# Backplane_extRefV4.net
KiCad netlist of a schematic drawn in EAGLE
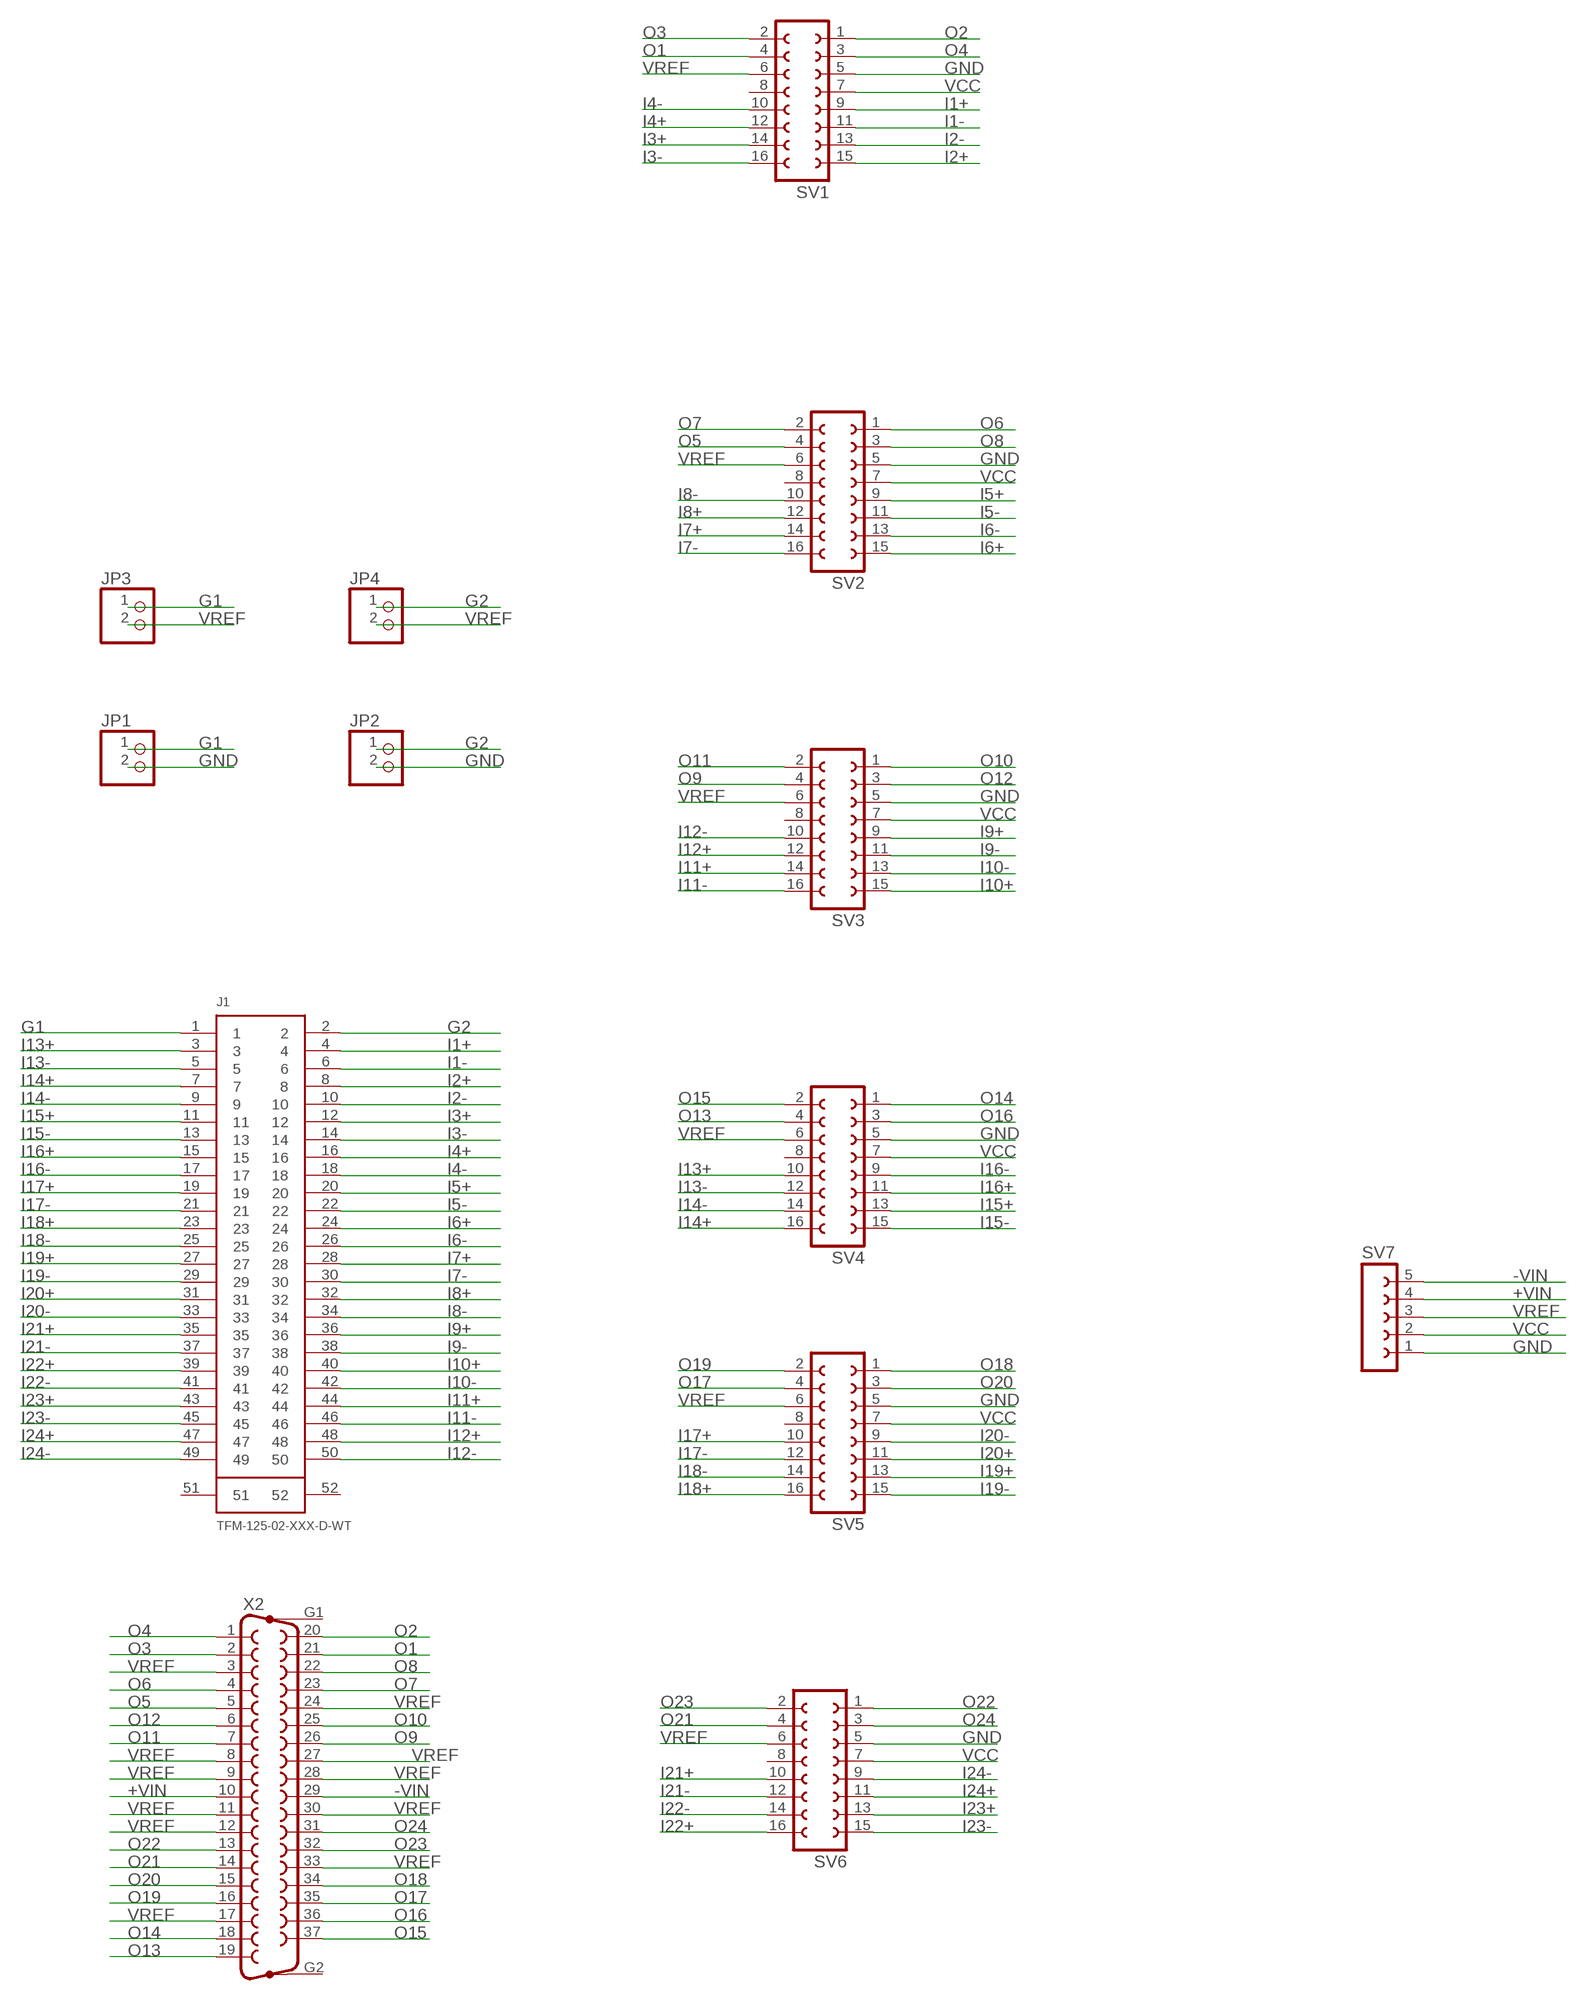
[diagram p0: schematic, sheet 1]

(export (version "E")
  (design (tool "Eeschema 10.0.6"))
  (components
    (comp (ref "J1")
      (value "TFM-125-02-XXX-D-WT")
      (footprint "eagle-import:TFM-125-02-XXX-D-WT")
      (libsource (lib "eagle-import") (part "TFM-125-02-XXX-D-WT"))
    )
    (comp (ref "JP1")
      (value "PINHD-1X2")
      (footprint "eagle-import:1X02")
      (libsource (lib "eagle-import") (part "PINHD-1X2"))
    )
    (comp (ref "JP2")
      (value "PINHD-1X2")
      (footprint "eagle-import:1X02")
      (libsource (lib "eagle-import") (part "PINHD-1X2"))
    )
    (comp (ref "JP3")
      (value "PINHD-1X2")
      (footprint "eagle-import:1X02")
      (libsource (lib "eagle-import") (part "PINHD-1X2"))
    )
    (comp (ref "JP4")
      (value "PINHD-1X2")
      (footprint "eagle-import:1X02")
      (libsource (lib "eagle-import") (part "PINHD-1X2"))
    )
    (comp (ref "SV1")
      (value "FE08-2")
      (footprint "eagle-import:FE08-2")
      (libsource (lib "eagle-import") (part "FE08-2"))
    )
    (comp (ref "SV2")
      (value "FE08-2")
      (footprint "eagle-import:FE08-2")
      (libsource (lib "eagle-import") (part "FE08-2"))
    )
    (comp (ref "SV3")
      (value "FE08-2")
      (footprint "eagle-import:FE08-2")
      (libsource (lib "eagle-import") (part "FE08-2"))
    )
    (comp (ref "SV4")
      (value "FE08-2")
      (footprint "eagle-import:FE08-2")
      (libsource (lib "eagle-import") (part "FE08-2"))
    )
    (comp (ref "SV5")
      (value "FE08-2")
      (footprint "eagle-import:FE08-2")
      (libsource (lib "eagle-import") (part "FE08-2"))
    )
    (comp (ref "SV6")
      (value "FE08-2")
      (footprint "eagle-import:FE08-2")
      (libsource (lib "eagle-import") (part "FE08-2"))
    )
    (comp (ref "SV7")
      (value "FE05-1")
      (footprint "eagle-import:FE05-1")
      (libsource (lib "eagle-import") (part "FE05-1"))
    )
    (comp (ref "X2")
      (value "F37HP")
      (footprint "eagle-import:F37HP")
      (libsource (lib "eagle-import") (part "F37HP"))
    )
  )
  (nets
    (net (code "1") (name "/+VIN") (class "Default")
      (node (ref "SV7") (pin "4") (pinfunction "4_4") (pintype "passive"))
      (node (ref "X2") (pin "10") (pinfunction "10_10") (pintype "passive"))
    )
    (net (code "2") (name "/-VIN") (class "Default")
      (node (ref "SV7") (pin "5") (pinfunction "5_5") (pintype "passive"))
      (node (ref "X2") (pin "29") (pinfunction "29_29") (pintype "passive"))
    )
    (net (code "3") (name "/G1") (class "Default")
      (node (ref "J1") (pin "1") (pinfunction "1_1") (pintype "bidirectional"))
      (node (ref "JP1") (pin "1") (pinfunction "1_1") (pintype "passive"))
      (node (ref "JP3") (pin "1") (pinfunction "1_1") (pintype "passive"))
    )
    (net (code "4") (name "/G2") (class "Default")
      (node (ref "J1") (pin "2") (pinfunction "2_2") (pintype "bidirectional"))
      (node (ref "JP2") (pin "1") (pinfunction "1_1") (pintype "passive"))
      (node (ref "JP4") (pin "1") (pinfunction "1_1") (pintype "passive"))
    )
    (net (code "5") (name "/GND") (class "Default")
      (node (ref "JP1") (pin "2") (pinfunction "2_2") (pintype "passive"))
      (node (ref "JP2") (pin "2") (pinfunction "2_2") (pintype "passive"))
      (node (ref "SV1") (pin "5") (pinfunction "5_5") (pintype "passive"))
      (node (ref "SV2") (pin "5") (pinfunction "5_5") (pintype "passive"))
      (node (ref "SV3") (pin "5") (pinfunction "5_5") (pintype "passive"))
      (node (ref "SV4") (pin "5") (pinfunction "5_5") (pintype "passive"))
      (node (ref "SV5") (pin "5") (pinfunction "5_5") (pintype "passive"))
      (node (ref "SV6") (pin "5") (pinfunction "5_5") (pintype "passive"))
      (node (ref "SV7") (pin "1") (pinfunction "1_1") (pintype "passive"))
    )
    (net (code "6") (name "/I1+") (class "Default")
      (node (ref "J1") (pin "4") (pinfunction "4_4") (pintype "bidirectional"))
      (node (ref "SV1") (pin "9") (pinfunction "9_9") (pintype "passive"))
    )
    (net (code "7") (name "/I1-") (class "Default")
      (node (ref "J1") (pin "6") (pinfunction "6_6") (pintype "bidirectional"))
      (node (ref "SV1") (pin "11") (pinfunction "11_11") (pintype "passive"))
    )
    (net (code "8") (name "/I2+") (class "Default")
      (node (ref "J1") (pin "8") (pinfunction "8_8") (pintype "bidirectional"))
      (node (ref "SV1") (pin "15") (pinfunction "15_15") (pintype "passive"))
    )
    (net (code "9") (name "/I2-") (class "Default")
      (node (ref "J1") (pin "10") (pinfunction "10_10") (pintype "bidirectional"))
      (node (ref "SV1") (pin "13") (pinfunction "13_13") (pintype "passive"))
    )
    (net (code "10") (name "/I3+") (class "Default")
      (node (ref "J1") (pin "12") (pinfunction "12_12") (pintype "bidirectional"))
      (node (ref "SV1") (pin "14") (pinfunction "14_14") (pintype "passive"))
    )
    (net (code "11") (name "/I3-") (class "Default")
      (node (ref "J1") (pin "14") (pinfunction "14_14") (pintype "bidirectional"))
      (node (ref "SV1") (pin "16") (pinfunction "16_16") (pintype "passive"))
    )
    (net (code "12") (name "/I4+") (class "Default")
      (node (ref "J1") (pin "16") (pinfunction "16_16") (pintype "bidirectional"))
      (node (ref "SV1") (pin "12") (pinfunction "12_12") (pintype "passive"))
    )
    (net (code "13") (name "/I4-") (class "Default")
      (node (ref "J1") (pin "18") (pinfunction "18_18") (pintype "bidirectional"))
      (node (ref "SV1") (pin "10") (pinfunction "10_10") (pintype "passive"))
    )
    (net (code "14") (name "/I5+") (class "Default")
      (node (ref "J1") (pin "20") (pinfunction "20_20") (pintype "bidirectional"))
      (node (ref "SV2") (pin "9") (pinfunction "9_9") (pintype "passive"))
    )
    (net (code "15") (name "/I5-") (class "Default")
      (node (ref "J1") (pin "22") (pinfunction "22_22") (pintype "bidirectional"))
      (node (ref "SV2") (pin "11") (pinfunction "11_11") (pintype "passive"))
    )
    (net (code "16") (name "/I6+") (class "Default")
      (node (ref "J1") (pin "24") (pinfunction "24_24") (pintype "bidirectional"))
      (node (ref "SV2") (pin "15") (pinfunction "15_15") (pintype "passive"))
    )
    (net (code "17") (name "/I6-") (class "Default")
      (node (ref "J1") (pin "26") (pinfunction "26_26") (pintype "bidirectional"))
      (node (ref "SV2") (pin "13") (pinfunction "13_13") (pintype "passive"))
    )
    (net (code "18") (name "/I7+") (class "Default")
      (node (ref "J1") (pin "28") (pinfunction "28_28") (pintype "bidirectional"))
      (node (ref "SV2") (pin "14") (pinfunction "14_14") (pintype "passive"))
    )
    (net (code "19") (name "/I7-") (class "Default")
      (node (ref "J1") (pin "30") (pinfunction "30_30") (pintype "bidirectional"))
      (node (ref "SV2") (pin "16") (pinfunction "16_16") (pintype "passive"))
    )
    (net (code "20") (name "/I8+") (class "Default")
      (node (ref "J1") (pin "32") (pinfunction "32_32") (pintype "bidirectional"))
      (node (ref "SV2") (pin "12") (pinfunction "12_12") (pintype "passive"))
    )
    (net (code "21") (name "/I8-") (class "Default")
      (node (ref "J1") (pin "34") (pinfunction "34_34") (pintype "bidirectional"))
      (node (ref "SV2") (pin "10") (pinfunction "10_10") (pintype "passive"))
    )
    (net (code "22") (name "/I9+") (class "Default")
      (node (ref "J1") (pin "36") (pinfunction "36_36") (pintype "bidirectional"))
      (node (ref "SV3") (pin "9") (pinfunction "9_9") (pintype "passive"))
    )
    (net (code "23") (name "/I9-") (class "Default")
      (node (ref "J1") (pin "38") (pinfunction "38_38") (pintype "bidirectional"))
      (node (ref "SV3") (pin "11") (pinfunction "11_11") (pintype "passive"))
    )
    (net (code "24") (name "/I10+") (class "Default")
      (node (ref "J1") (pin "40") (pinfunction "40_40") (pintype "bidirectional"))
      (node (ref "SV3") (pin "15") (pinfunction "15_15") (pintype "passive"))
    )
    (net (code "25") (name "/I10-") (class "Default")
      (node (ref "J1") (pin "42") (pinfunction "42_42") (pintype "bidirectional"))
      (node (ref "SV3") (pin "13") (pinfunction "13_13") (pintype "passive"))
    )
    (net (code "26") (name "/I11+") (class "Default")
      (node (ref "J1") (pin "44") (pinfunction "44_44") (pintype "bidirectional"))
      (node (ref "SV3") (pin "14") (pinfunction "14_14") (pintype "passive"))
    )
    (net (code "27") (name "/I11-") (class "Default")
      (node (ref "J1") (pin "46") (pinfunction "46_46") (pintype "bidirectional"))
      (node (ref "SV3") (pin "16") (pinfunction "16_16") (pintype "passive"))
    )
    (net (code "28") (name "/I12+") (class "Default")
      (node (ref "J1") (pin "48") (pinfunction "48_48") (pintype "bidirectional"))
      (node (ref "SV3") (pin "12") (pinfunction "12_12") (pintype "passive"))
    )
    (net (code "29") (name "/I12-") (class "Default")
      (node (ref "J1") (pin "50") (pinfunction "50_50") (pintype "bidirectional"))
      (node (ref "SV3") (pin "10") (pinfunction "10_10") (pintype "passive"))
    )
    (net (code "30") (name "/I13+") (class "Default")
      (node (ref "J1") (pin "3") (pinfunction "3_3") (pintype "bidirectional"))
      (node (ref "SV4") (pin "10") (pinfunction "10_10") (pintype "passive"))
    )
    (net (code "31") (name "/I13-") (class "Default")
      (node (ref "J1") (pin "5") (pinfunction "5_5") (pintype "bidirectional"))
      (node (ref "SV4") (pin "12") (pinfunction "12_12") (pintype "passive"))
    )
    (net (code "32") (name "/I14+") (class "Default")
      (node (ref "J1") (pin "7") (pinfunction "7_7") (pintype "bidirectional"))
      (node (ref "SV4") (pin "16") (pinfunction "16_16") (pintype "passive"))
    )
    (net (code "33") (name "/I14-") (class "Default")
      (node (ref "J1") (pin "9") (pinfunction "9_9") (pintype "bidirectional"))
      (node (ref "SV4") (pin "14") (pinfunction "14_14") (pintype "passive"))
    )
    (net (code "34") (name "/I15+") (class "Default")
      (node (ref "J1") (pin "11") (pinfunction "11_11") (pintype "bidirectional"))
      (node (ref "SV4") (pin "13") (pinfunction "13_13") (pintype "passive"))
    )
    (net (code "35") (name "/I15-") (class "Default")
      (node (ref "J1") (pin "13") (pinfunction "13_13") (pintype "bidirectional"))
      (node (ref "SV4") (pin "15") (pinfunction "15_15") (pintype "passive"))
    )
    (net (code "36") (name "/I16+") (class "Default")
      (node (ref "J1") (pin "15") (pinfunction "15_15") (pintype "bidirectional"))
      (node (ref "SV4") (pin "11") (pinfunction "11_11") (pintype "passive"))
    )
    (net (code "37") (name "/I16-") (class "Default")
      (node (ref "J1") (pin "17") (pinfunction "17_17") (pintype "bidirectional"))
      (node (ref "SV4") (pin "9") (pinfunction "9_9") (pintype "passive"))
    )
    (net (code "38") (name "/I17+") (class "Default")
      (node (ref "J1") (pin "19") (pinfunction "19_19") (pintype "bidirectional"))
      (node (ref "SV5") (pin "10") (pinfunction "10_10") (pintype "passive"))
    )
    (net (code "39") (name "/I17-") (class "Default")
      (node (ref "J1") (pin "21") (pinfunction "21_21") (pintype "bidirectional"))
      (node (ref "SV5") (pin "12") (pinfunction "12_12") (pintype "passive"))
    )
    (net (code "40") (name "/I18+") (class "Default")
      (node (ref "J1") (pin "23") (pinfunction "23_23") (pintype "bidirectional"))
      (node (ref "SV5") (pin "16") (pinfunction "16_16") (pintype "passive"))
    )
    (net (code "41") (name "/I18-") (class "Default")
      (node (ref "J1") (pin "25") (pinfunction "25_25") (pintype "bidirectional"))
      (node (ref "SV5") (pin "14") (pinfunction "14_14") (pintype "passive"))
    )
    (net (code "42") (name "/I19+") (class "Default")
      (node (ref "J1") (pin "27") (pinfunction "27_27") (pintype "bidirectional"))
      (node (ref "SV5") (pin "13") (pinfunction "13_13") (pintype "passive"))
    )
    (net (code "43") (name "/I19-") (class "Default")
      (node (ref "J1") (pin "29") (pinfunction "29_29") (pintype "bidirectional"))
      (node (ref "SV5") (pin "15") (pinfunction "15_15") (pintype "passive"))
    )
    (net (code "44") (name "/I20+") (class "Default")
      (node (ref "J1") (pin "31") (pinfunction "31_31") (pintype "bidirectional"))
      (node (ref "SV5") (pin "11") (pinfunction "11_11") (pintype "passive"))
    )
    (net (code "45") (name "/I20-") (class "Default")
      (node (ref "J1") (pin "33") (pinfunction "33_33") (pintype "bidirectional"))
      (node (ref "SV5") (pin "9") (pinfunction "9_9") (pintype "passive"))
    )
    (net (code "46") (name "/I21+") (class "Default")
      (node (ref "J1") (pin "35") (pinfunction "35_35") (pintype "bidirectional"))
      (node (ref "SV6") (pin "10") (pinfunction "10_10") (pintype "passive"))
    )
    (net (code "47") (name "/I21-") (class "Default")
      (node (ref "J1") (pin "37") (pinfunction "37_37") (pintype "bidirectional"))
      (node (ref "SV6") (pin "12") (pinfunction "12_12") (pintype "passive"))
    )
    (net (code "48") (name "/I22+") (class "Default")
      (node (ref "J1") (pin "39") (pinfunction "39_39") (pintype "bidirectional"))
      (node (ref "SV6") (pin "16") (pinfunction "16_16") (pintype "passive"))
    )
    (net (code "49") (name "/I22-") (class "Default")
      (node (ref "J1") (pin "41") (pinfunction "41_41") (pintype "bidirectional"))
      (node (ref "SV6") (pin "14") (pinfunction "14_14") (pintype "passive"))
    )
    (net (code "50") (name "/I23+") (class "Default")
      (node (ref "J1") (pin "43") (pinfunction "43_43") (pintype "bidirectional"))
      (node (ref "SV6") (pin "13") (pinfunction "13_13") (pintype "passive"))
    )
    (net (code "51") (name "/I23-") (class "Default")
      (node (ref "J1") (pin "45") (pinfunction "45_45") (pintype "bidirectional"))
      (node (ref "SV6") (pin "15") (pinfunction "15_15") (pintype "passive"))
    )
    (net (code "52") (name "/I24+") (class "Default")
      (node (ref "J1") (pin "47") (pinfunction "47_47") (pintype "bidirectional"))
      (node (ref "SV6") (pin "11") (pinfunction "11_11") (pintype "passive"))
    )
    (net (code "53") (name "/I24-") (class "Default")
      (node (ref "J1") (pin "49") (pinfunction "49_49") (pintype "bidirectional"))
      (node (ref "SV6") (pin "9") (pinfunction "9_9") (pintype "passive"))
    )
    (net (code "54") (name "/O1") (class "Default")
      (node (ref "SV1") (pin "4") (pinfunction "4_4") (pintype "passive"))
      (node (ref "X2") (pin "21") (pinfunction "21_21") (pintype "passive"))
    )
    (net (code "55") (name "/O2") (class "Default")
      (node (ref "SV1") (pin "1") (pinfunction "1_1") (pintype "passive"))
      (node (ref "X2") (pin "20") (pinfunction "20_20") (pintype "passive"))
    )
    (net (code "56") (name "/O3") (class "Default")
      (node (ref "SV1") (pin "2") (pinfunction "2_2") (pintype "passive"))
      (node (ref "X2") (pin "2") (pinfunction "2_2") (pintype "passive"))
    )
    (net (code "57") (name "/O4") (class "Default")
      (node (ref "SV1") (pin "3") (pinfunction "3_3") (pintype "passive"))
      (node (ref "X2") (pin "1") (pinfunction "1_1") (pintype "passive"))
    )
    (net (code "58") (name "/O5") (class "Default")
      (node (ref "SV2") (pin "4") (pinfunction "4_4") (pintype "passive"))
      (node (ref "X2") (pin "5") (pinfunction "5_5") (pintype "passive"))
    )
    (net (code "59") (name "/O6") (class "Default")
      (node (ref "SV2") (pin "1") (pinfunction "1_1") (pintype "passive"))
      (node (ref "X2") (pin "4") (pinfunction "4_4") (pintype "passive"))
    )
    (net (code "60") (name "/O7") (class "Default")
      (node (ref "SV2") (pin "2") (pinfunction "2_2") (pintype "passive"))
      (node (ref "X2") (pin "23") (pinfunction "23_23") (pintype "passive"))
    )
    (net (code "61") (name "/O8") (class "Default")
      (node (ref "SV2") (pin "3") (pinfunction "3_3") (pintype "passive"))
      (node (ref "X2") (pin "22") (pinfunction "22_22") (pintype "passive"))
    )
    (net (code "62") (name "/O9") (class "Default")
      (node (ref "SV3") (pin "4") (pinfunction "4_4") (pintype "passive"))
      (node (ref "X2") (pin "26") (pinfunction "26_26") (pintype "passive"))
    )
    (net (code "63") (name "/O10") (class "Default")
      (node (ref "SV3") (pin "1") (pinfunction "1_1") (pintype "passive"))
      (node (ref "X2") (pin "25") (pinfunction "25_25") (pintype "passive"))
    )
    (net (code "64") (name "/O11") (class "Default")
      (node (ref "SV3") (pin "2") (pinfunction "2_2") (pintype "passive"))
      (node (ref "X2") (pin "7") (pinfunction "7_7") (pintype "passive"))
    )
    (net (code "65") (name "/O12") (class "Default")
      (node (ref "SV3") (pin "3") (pinfunction "3_3") (pintype "passive"))
      (node (ref "X2") (pin "6") (pinfunction "6_6") (pintype "passive"))
    )
    (net (code "66") (name "/O13") (class "Default")
      (node (ref "SV4") (pin "4") (pinfunction "4_4") (pintype "passive"))
      (node (ref "X2") (pin "19") (pinfunction "19_19") (pintype "passive"))
    )
    (net (code "67") (name "/O14") (class "Default")
      (node (ref "SV4") (pin "1") (pinfunction "1_1") (pintype "passive"))
      (node (ref "X2") (pin "18") (pinfunction "18_18") (pintype "passive"))
    )
    (net (code "68") (name "/O15") (class "Default")
      (node (ref "SV4") (pin "2") (pinfunction "2_2") (pintype "passive"))
      (node (ref "X2") (pin "37") (pinfunction "37_37") (pintype "passive"))
    )
    (net (code "69") (name "/O16") (class "Default")
      (node (ref "SV4") (pin "3") (pinfunction "3_3") (pintype "passive"))
      (node (ref "X2") (pin "36") (pinfunction "36_36") (pintype "passive"))
    )
    (net (code "70") (name "/O17") (class "Default")
      (node (ref "SV5") (pin "4") (pinfunction "4_4") (pintype "passive"))
      (node (ref "X2") (pin "35") (pinfunction "35_35") (pintype "passive"))
    )
    (net (code "71") (name "/O18") (class "Default")
      (node (ref "SV5") (pin "1") (pinfunction "1_1") (pintype "passive"))
      (node (ref "X2") (pin "34") (pinfunction "34_34") (pintype "passive"))
    )
    (net (code "72") (name "/O19") (class "Default")
      (node (ref "SV5") (pin "2") (pinfunction "2_2") (pintype "passive"))
      (node (ref "X2") (pin "16") (pinfunction "16_16") (pintype "passive"))
    )
    (net (code "73") (name "/O20") (class "Default")
      (node (ref "SV5") (pin "3") (pinfunction "3_3") (pintype "passive"))
      (node (ref "X2") (pin "15") (pinfunction "15_15") (pintype "passive"))
    )
    (net (code "74") (name "/O21") (class "Default")
      (node (ref "SV6") (pin "4") (pinfunction "4_4") (pintype "passive"))
      (node (ref "X2") (pin "14") (pinfunction "14_14") (pintype "passive"))
    )
    (net (code "75") (name "/O22") (class "Default")
      (node (ref "SV6") (pin "1") (pinfunction "1_1") (pintype "passive"))
      (node (ref "X2") (pin "13") (pinfunction "13_13") (pintype "passive"))
    )
    (net (code "76") (name "/O23") (class "Default")
      (node (ref "SV6") (pin "2") (pinfunction "2_2") (pintype "passive"))
      (node (ref "X2") (pin "32") (pinfunction "32_32") (pintype "passive"))
    )
    (net (code "77") (name "/O24") (class "Default")
      (node (ref "SV6") (pin "3") (pinfunction "3_3") (pintype "passive"))
      (node (ref "X2") (pin "31") (pinfunction "31_31") (pintype "passive"))
    )
    (net (code "78") (name "/VCC") (class "Default")
      (node (ref "SV1") (pin "7") (pinfunction "7_7") (pintype "passive"))
      (node (ref "SV2") (pin "7") (pinfunction "7_7") (pintype "passive"))
      (node (ref "SV3") (pin "7") (pinfunction "7_7") (pintype "passive"))
      (node (ref "SV4") (pin "7") (pinfunction "7_7") (pintype "passive"))
      (node (ref "SV5") (pin "7") (pinfunction "7_7") (pintype "passive"))
      (node (ref "SV6") (pin "7") (pinfunction "7_7") (pintype "passive"))
      (node (ref "SV7") (pin "2") (pinfunction "2_2") (pintype "passive"))
    )
    (net (code "79") (name "/VREF") (class "Default")
      (node (ref "JP3") (pin "2") (pinfunction "2_2") (pintype "passive"))
      (node (ref "JP4") (pin "2") (pinfunction "2_2") (pintype "passive"))
      (node (ref "SV1") (pin "6") (pinfunction "6_6") (pintype "passive"))
      (node (ref "SV2") (pin "6") (pinfunction "6_6") (pintype "passive"))
      (node (ref "SV3") (pin "6") (pinfunction "6_6") (pintype "passive"))
      (node (ref "SV4") (pin "6") (pinfunction "6_6") (pintype "passive"))
      (node (ref "SV5") (pin "6") (pinfunction "6_6") (pintype "passive"))
      (node (ref "SV6") (pin "6") (pinfunction "6_6") (pintype "passive"))
      (node (ref "SV7") (pin "3") (pinfunction "3_3") (pintype "passive"))
      (node (ref "X2") (pin "11") (pinfunction "11_11") (pintype "passive"))
      (node (ref "X2") (pin "12") (pinfunction "12_12") (pintype "passive"))
      (node (ref "X2") (pin "17") (pinfunction "17_17") (pintype "passive"))
      (node (ref "X2") (pin "24") (pinfunction "24_24") (pintype "passive"))
      (node (ref "X2") (pin "27") (pinfunction "27_27") (pintype "passive"))
      (node (ref "X2") (pin "28") (pinfunction "28_28") (pintype "passive"))
      (node (ref "X2") (pin "3") (pinfunction "3_3") (pintype "passive"))
      (node (ref "X2") (pin "30") (pinfunction "30_30") (pintype "passive"))
      (node (ref "X2") (pin "33") (pinfunction "33_33") (pintype "passive"))
      (node (ref "X2") (pin "8") (pinfunction "8_8") (pintype "passive"))
      (node (ref "X2") (pin "9") (pinfunction "9_9") (pintype "passive"))
    )
    (net (code "80") (name "unconnected-(J1-Pad51)") (class "Default")
      (node (ref "J1") (pin "51") (pinfunction "51_51") (pintype "bidirectional"))
    )
    (net (code "81") (name "unconnected-(J1-Pad52)") (class "Default")
      (node (ref "J1") (pin "52") (pinfunction "52_52") (pintype "bidirectional"))
    )
    (net (code "82") (name "unconnected-(SV1-Pad8)") (class "Default")
      (node (ref "SV1") (pin "8") (pinfunction "8_8") (pintype "passive"))
    )
    (net (code "83") (name "unconnected-(SV2-Pad8)") (class "Default")
      (node (ref "SV2") (pin "8") (pinfunction "8_8") (pintype "passive"))
    )
    (net (code "84") (name "unconnected-(SV3-Pad8)") (class "Default")
      (node (ref "SV3") (pin "8") (pinfunction "8_8") (pintype "passive"))
    )
    (net (code "85") (name "unconnected-(SV4-Pad8)") (class "Default")
      (node (ref "SV4") (pin "8") (pinfunction "8_8") (pintype "passive"))
    )
    (net (code "86") (name "unconnected-(SV5-Pad8)") (class "Default")
      (node (ref "SV5") (pin "8") (pinfunction "8_8") (pintype "passive"))
    )
    (net (code "87") (name "unconnected-(SV6-Pad8)") (class "Default")
      (node (ref "SV6") (pin "8") (pinfunction "8_8") (pintype "passive"))
    )
    (net (code "88") (name "unconnected-(X2-PadG1)") (class "Default")
      (node (ref "X2") (pin "G1") (pinfunction "G1_G1") (pintype "passive"))
    )
    (net (code "89") (name "unconnected-(X2-PadG2)") (class "Default")
      (node (ref "X2") (pin "G2") (pinfunction "G2_G2") (pintype "passive"))
    )
  )
)
